# uno.net
KiCad netlist of a schematic drawn in EAGLE
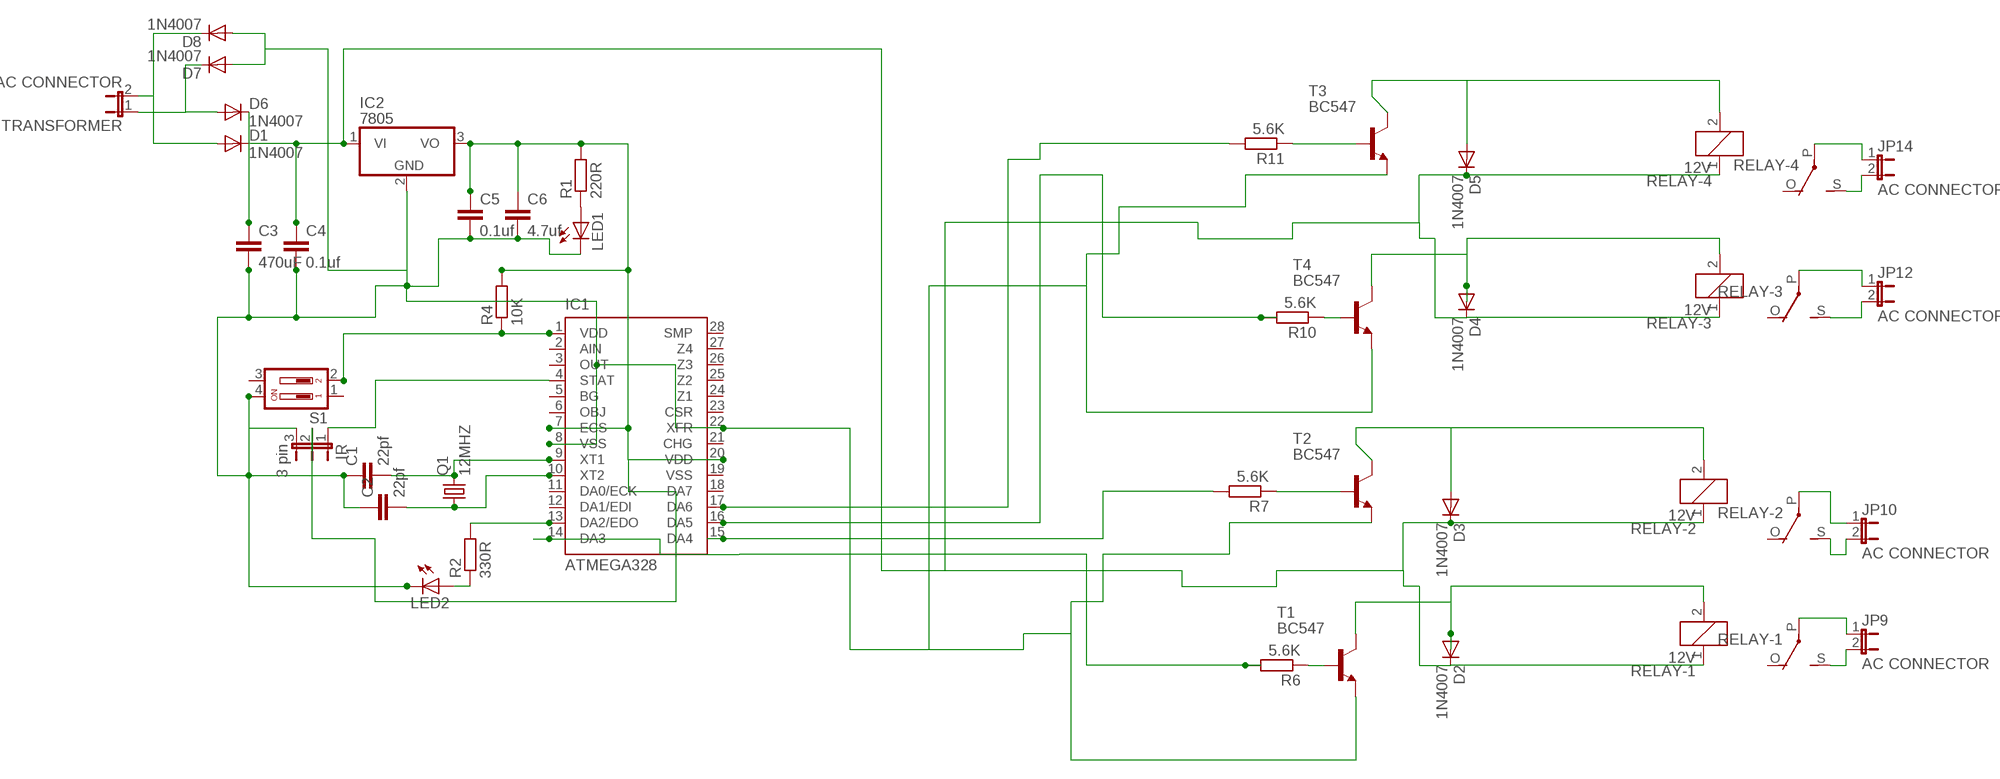
[diagram p0: schematic, sheet 1]

(export (version "E")
  (design (tool "Eeschema 10.0.6"))
  (components
    (comp (ref "C1")
      (value "22pf")
      (footprint "eagle-import:C2.5-2")
      (libsource (lib "eagle-import") (part "C2.5/2"))
    )
    (comp (ref "C2")
      (value "22pf")
      (footprint "eagle-import:C2.5-2")
      (libsource (lib "eagle-import") (part "C2.5/2"))
    )
    (comp (ref "C3")
      (value "470uF")
      (footprint "eagle-import:C2.5-2")
      (libsource (lib "eagle-import") (part "C2.5/2"))
    )
    (comp (ref "C4")
      (value "0.1uf")
      (footprint "eagle-import:C2.5-2")
      (libsource (lib "eagle-import") (part "C2.5/2"))
    )
    (comp (ref "C5")
      (value "0.1uf")
      (footprint "eagle-import:C2.5-2")
      (libsource (lib "eagle-import") (part "C2.5/2"))
    )
    (comp (ref "C6")
      (value "4.7uf")
      (footprint "eagle-import:C2.5-2")
      (libsource (lib "eagle-import") (part "C2.5/2"))
    )
    (comp (ref "D1")
      (value "1N4007")
      (footprint "eagle-import:DO41-10")
      (libsource (lib "eagle-import") (part "1N4004"))
    )
    (comp (ref "D2")
      (value "1N4007")
      (footprint "eagle-import:DO41-10")
      (libsource (lib "eagle-import") (part "1N4004"))
    )
    (comp (ref "D3")
      (value "1N4007")
      (footprint "eagle-import:DO41-10")
      (libsource (lib "eagle-import") (part "1N4004"))
    )
    (comp (ref "D4")
      (value "1N4007")
      (footprint "eagle-import:DO41-10")
      (libsource (lib "eagle-import") (part "1N4004"))
    )
    (comp (ref "D5")
      (value "1N4007")
      (footprint "eagle-import:DO41-10")
      (libsource (lib "eagle-import") (part "1N4004"))
    )
    (comp (ref "D6")
      (value "1N4007")
      (footprint "eagle-import:DO41-10")
      (libsource (lib "eagle-import") (part "1N4004"))
    )
    (comp (ref "D7")
      (value "1N4007")
      (footprint "eagle-import:DO41-10")
      (libsource (lib "eagle-import") (part "1N4004"))
    )
    (comp (ref "D8")
      (value "1N4007")
      (footprint "eagle-import:DO41-10")
      (libsource (lib "eagle-import") (part "1N4004"))
    )
    (comp (ref "IC1")
      (value "ATMEGA328")
      (footprint "eagle-import:DIL28-3")
      (libsource (lib "eagle-import") (part "QT9701BD"))
    )
    (comp (ref "IC2")
      (value "7805")
      (footprint "eagle-import:TO220V")
      (libsource (lib "eagle-import") (part "78TV6"))
    )
    (comp (ref "IR")
      (value "3 pin")
      (footprint "eagle-import:JP2")
      (libsource (lib "eagle-import") (part "JP2E"))
    )
    (comp (ref "JP9")
      (value "AC CONNECTOR")
      (footprint "eagle-import:JP1")
      (libsource (lib "eagle-import") (part "JP1E"))
    )
    (comp (ref "JP10")
      (value "AC CONNECTOR")
      (footprint "eagle-import:JP1")
      (libsource (lib "eagle-import") (part "JP1E"))
    )
    (comp (ref "JP12")
      (value "AC CONNECTOR")
      (footprint "eagle-import:JP1")
      (libsource (lib "eagle-import") (part "JP1E"))
    )
    (comp (ref "JP14")
      (value "AC CONNECTOR")
      (footprint "eagle-import:JP1")
      (libsource (lib "eagle-import") (part "JP1E"))
    )
    (comp (ref "LED1")
      (value "LED3MM")
      (footprint "eagle-import:LED3MM")
      (libsource (lib "eagle-import") (part "LED3MM"))
    )
    (comp (ref "LED2")
      (value "LED3MM")
      (footprint "eagle-import:LED3MM")
      (libsource (lib "eagle-import") (part "LED3MM"))
    )
    (comp (ref "Q1")
      (value "12MHZ")
      (footprint "eagle-import:HC49_S")
      (libsource (lib "eagle-import") (part "CRYSTALHC49S"))
    )
    (comp (ref "R1")
      (value "220R")
      (footprint "eagle-import:0207_10")
      (libsource (lib "eagle-import") (part "R-EU_0207/10"))
    )
    (comp (ref "R2")
      (value "330R")
      (footprint "eagle-import:0207_10")
      (libsource (lib "eagle-import") (part "R-EU_0207/10"))
    )
    (comp (ref "R4")
      (value "10K")
      (footprint "eagle-import:0207_10")
      (libsource (lib "eagle-import") (part "R-EU_0207/10"))
    )
    (comp (ref "R6")
      (value "5.6K")
      (footprint "eagle-import:0204_7")
      (libsource (lib "eagle-import") (part "R-EU_0204/7"))
    )
    (comp (ref "R7")
      (value "5.6K")
      (footprint "eagle-import:0204_7")
      (libsource (lib "eagle-import") (part "R-EU_0204/7"))
    )
    (comp (ref "R10")
      (value "5.6K")
      (footprint "eagle-import:0204_7")
      (libsource (lib "eagle-import") (part "R-EU_0204/7"))
    )
    (comp (ref "R11")
      (value "5.6K")
      (footprint "eagle-import:0204_7")
      (libsource (lib "eagle-import") (part "R-EU_0204/7"))
    )
    (comp (ref "RELAY-1")
      (value "12V")
      (footprint "eagle-import:G5LE")
      (libsource (lib "eagle-import") (part "G5L"))
    )
    (comp (ref "RELAY-2")
      (value "12V")
      (footprint "eagle-import:G5LE")
      (libsource (lib "eagle-import") (part "G5L"))
    )
    (comp (ref "RELAY-3")
      (value "12V")
      (footprint "eagle-import:G5LE")
      (libsource (lib "eagle-import") (part "G5L"))
    )
    (comp (ref "RELAY-4")
      (value "12V")
      (footprint "eagle-import:G5LE")
      (libsource (lib "eagle-import") (part "G5L"))
    )
    (comp (ref "S1")
      (value "DP02")
      (footprint "eagle-import:DP-02")
      (fields (field (name "MPN") "MCDP02"))
      (libsource (lib "eagle-import") (part "DP02"))
    )
    (comp (ref "T1")
      (value "BC547")
      (footprint "eagle-import:TO92")
      (libsource (lib "eagle-import") (part "BC547"))
    )
    (comp (ref "T2")
      (value "BC547")
      (footprint "eagle-import:TO92")
      (libsource (lib "eagle-import") (part "BC547"))
    )
    (comp (ref "T3")
      (value "BC547")
      (footprint "eagle-import:TO92")
      (libsource (lib "eagle-import") (part "BC547"))
    )
    (comp (ref "T4")
      (value "BC547")
      (footprint "eagle-import:TO92")
      (libsource (lib "eagle-import") (part "BC547"))
    )
    (comp (ref "TRANSFORMER")
      (value "AC CONNECTOR")
      (footprint "eagle-import:JP1")
      (libsource (lib "eagle-import") (part "JP1E"))
    )
  )
  (nets
    (net (code "1") (name "Net-(D1-PadA)") (class "Default")
      (node (ref "D1") (pin "A") (pinfunction "A_A") (pintype "passive"))
      (node (ref "D8") (pin "C") (pinfunction "C_C") (pintype "passive"))
      (node (ref "TRANSFORMER") (pin "2") (pinfunction "2_2") (pintype "passive"))
    )
    (net (code "2") (name "Net-(D6-PadA)") (class "Default")
      (node (ref "D6") (pin "A") (pinfunction "A_A") (pintype "passive"))
      (node (ref "D7") (pin "C") (pinfunction "C_C") (pintype "passive"))
      (node (ref "TRANSFORMER") (pin "1") (pinfunction "1_1") (pintype "passive"))
    )
    (net (code "3") (name "Net-(IC1-DA2{slash}EDO)") (class "Default")
      (node (ref "IC1") (pin "13") (pinfunction "DA2/EDO_13") (pintype "output"))
      (node (ref "R2") (pin "2") (pinfunction "2_2") (pintype "passive"))
    )
    (net (code "4") (name "Net-(IC1-DA3)") (class "Default")
      (node (ref "IC1") (pin "14") (pinfunction "DA3_14") (pintype "output"))
      (node (ref "R6") (pin "2") (pinfunction "2_2") (pintype "passive"))
    )
    (net (code "5") (name "Net-(IC1-DA4)") (class "Default")
      (node (ref "IC1") (pin "15") (pinfunction "DA4_15") (pintype "output"))
      (node (ref "R7") (pin "2") (pinfunction "2_2") (pintype "passive"))
    )
    (net (code "6") (name "Net-(IC1-DA5)") (class "Default")
      (node (ref "IC1") (pin "16") (pinfunction "DA5_16") (pintype "output"))
      (node (ref "R10") (pin "2") (pinfunction "2_2") (pintype "passive"))
    )
    (net (code "7") (name "Net-(IC1-DA6)") (class "Default")
      (node (ref "IC1") (pin "17") (pinfunction "DA6_17") (pintype "output"))
      (node (ref "R11") (pin "2") (pinfunction "2_2") (pintype "passive"))
    )
    (net (code "8") (name "Net-(IC1-ECS)") (class "Default")
      (node (ref "C5") (pin "1") (pinfunction "1_1") (pintype "passive"))
      (node (ref "C6") (pin "1") (pinfunction "1_1") (pintype "passive"))
      (node (ref "IC1") (pin "20") (pinfunction "VDD_20") (pintype "input"))
      (node (ref "IC1") (pin "7") (pinfunction "ECS_7") (pintype "output"))
      (node (ref "IC2") (pin "3") (pinfunction "VO_3") (pintype "passive"))
      (node (ref "IR") (pin "2") (pinfunction "2_2") (pintype "passive"))
      (node (ref "R1") (pin "2") (pinfunction "2_2") (pintype "passive"))
      (node (ref "R4") (pin "2") (pinfunction "2_2") (pintype "passive"))
    )
    (net (code "9") (name "Net-(IC1-STAT)") (class "Default")
      (node (ref "IC1") (pin "4") (pinfunction "STAT_4") (pintype "output"))
      (node (ref "IR") (pin "1") (pinfunction "1_1") (pintype "passive"))
    )
    (net (code "10") (name "Net-(IC1-VDD-Pad1)") (class "Default")
      (node (ref "IC1") (pin "1") (pinfunction "VDD_1") (pintype "input"))
      (node (ref "R4") (pin "1") (pinfunction "1_1") (pintype "passive"))
      (node (ref "S1") (pin "2") (pinfunction "2_2") (pintype "passive"))
    )
    (net (code "11") (name "Net-(IC1-XFR)") (class "Default")
      (node (ref "C1") (pin "1") (pinfunction "1_1") (pintype "passive"))
      (node (ref "C2") (pin "1") (pinfunction "1_1") (pintype "passive"))
      (node (ref "C3") (pin "2") (pinfunction "2_2") (pintype "passive"))
      (node (ref "C4") (pin "2") (pinfunction "2_2") (pintype "passive"))
      (node (ref "C5") (pin "2") (pinfunction "2_2") (pintype "passive"))
      (node (ref "C6") (pin "2") (pinfunction "2_2") (pintype "passive"))
      (node (ref "D7") (pin "A") (pinfunction "A_A") (pintype "passive"))
      (node (ref "D8") (pin "A") (pinfunction "A_A") (pintype "passive"))
      (node (ref "IC1") (pin "22") (pinfunction "XFR_22") (pintype "output"))
      (node (ref "IC1") (pin "8") (pinfunction "VSS_8") (pintype "input"))
      (node (ref "IC2") (pin "2") (pinfunction "GND_2") (pintype "passive"))
      (node (ref "IR") (pin "3") (pinfunction "3_3") (pintype "passive"))
      (node (ref "LED1") (pin "K") (pinfunction "C_K") (pintype "passive"))
      (node (ref "LED2") (pin "K") (pinfunction "C_K") (pintype "passive"))
      (node (ref "S1") (pin "4") (pinfunction "4_4") (pintype "passive"))
      (node (ref "T1") (pin "1") (pinfunction "E_1") (pintype "passive"))
      (node (ref "T2") (pin "1") (pinfunction "E_1") (pintype "passive"))
      (node (ref "T3") (pin "1") (pinfunction "E_1") (pintype "passive"))
      (node (ref "T4") (pin "1") (pinfunction "E_1") (pintype "passive"))
    )
    (net (code "12") (name "Net-(IC1-XT1)") (class "Default")
      (node (ref "C1") (pin "2") (pinfunction "2_2") (pintype "passive"))
      (node (ref "IC1") (pin "9") (pinfunction "XT1_9") (pintype "input"))
      (node (ref "Q1") (pin "2") (pinfunction "2_2") (pintype "passive"))
    )
    (net (code "13") (name "Net-(IC1-XT2)") (class "Default")
      (node (ref "C2") (pin "2") (pinfunction "2_2") (pintype "passive"))
      (node (ref "IC1") (pin "10") (pinfunction "XT2_10") (pintype "output"))
      (node (ref "Q1") (pin "1") (pinfunction "1_1") (pintype "passive"))
    )
    (net (code "14") (name "Net-(IC2-VI)") (class "Default")
      (node (ref "C3") (pin "1") (pinfunction "1_1") (pintype "passive"))
      (node (ref "C4") (pin "1") (pinfunction "1_1") (pintype "passive"))
      (node (ref "D1") (pin "C") (pinfunction "C_C") (pintype "passive"))
      (node (ref "D2") (pin "C") (pinfunction "C_C") (pintype "passive"))
      (node (ref "D3") (pin "C") (pinfunction "C_C") (pintype "passive"))
      (node (ref "D4") (pin "C") (pinfunction "C_C") (pintype "passive"))
      (node (ref "D5") (pin "C") (pinfunction "C_C") (pintype "passive"))
      (node (ref "D6") (pin "C") (pinfunction "C_C") (pintype "passive"))
      (node (ref "IC2") (pin "1") (pinfunction "VI_1") (pintype "input"))
      (node (ref "RELAY-1") (pin "1") (pinfunction "1_1") (pintype "passive"))
      (node (ref "RELAY-2") (pin "1") (pinfunction "1_1") (pintype "passive"))
      (node (ref "RELAY-3") (pin "1") (pinfunction "1_1") (pintype "passive"))
      (node (ref "RELAY-4") (pin "1") (pinfunction "1_1") (pintype "passive"))
    )
    (net (code "15") (name "Net-(JP9-Pad1)") (class "Default")
      (node (ref "JP9") (pin "1") (pinfunction "1_1") (pintype "passive"))
      (node (ref "RELAY-1") (pin "P") (pinfunction "P_P") (pintype "passive"))
    )
    (net (code "16") (name "Net-(JP9-Pad2)") (class "Default")
      (node (ref "JP9") (pin "2") (pinfunction "2_2") (pintype "passive"))
      (node (ref "RELAY-1") (pin "S") (pinfunction "S_S") (pintype "passive"))
    )
    (net (code "17") (name "Net-(JP10-Pad1)") (class "Default")
      (node (ref "JP10") (pin "1") (pinfunction "1_1") (pintype "passive"))
      (node (ref "RELAY-2") (pin "P") (pinfunction "P_P") (pintype "passive"))
    )
    (net (code "18") (name "Net-(JP10-Pad2)") (class "Default")
      (node (ref "JP10") (pin "2") (pinfunction "2_2") (pintype "passive"))
      (node (ref "RELAY-2") (pin "S") (pinfunction "S_S") (pintype "passive"))
    )
    (net (code "19") (name "Net-(JP12-Pad1)") (class "Default")
      (node (ref "JP12") (pin "1") (pinfunction "1_1") (pintype "passive"))
      (node (ref "RELAY-3") (pin "P") (pinfunction "P_P") (pintype "passive"))
    )
    (net (code "20") (name "Net-(JP12-Pad2)") (class "Default")
      (node (ref "JP12") (pin "2") (pinfunction "2_2") (pintype "passive"))
      (node (ref "RELAY-3") (pin "S") (pinfunction "S_S") (pintype "passive"))
    )
    (net (code "21") (name "Net-(JP14-Pad1)") (class "Default")
      (node (ref "JP14") (pin "1") (pinfunction "1_1") (pintype "passive"))
      (node (ref "RELAY-4") (pin "P") (pinfunction "P_P") (pintype "passive"))
    )
    (net (code "22") (name "Net-(JP14-Pad2)") (class "Default")
      (node (ref "JP14") (pin "2") (pinfunction "2_2") (pintype "passive"))
      (node (ref "RELAY-4") (pin "S") (pinfunction "S_S") (pintype "passive"))
    )
    (net (code "23") (name "Net-(LED1-PadA)") (class "Default")
      (node (ref "LED1") (pin "A") (pinfunction "A_A") (pintype "passive"))
      (node (ref "R1") (pin "1") (pinfunction "1_1") (pintype "passive"))
    )
    (net (code "24") (name "Net-(LED2-PadA)") (class "Default")
      (node (ref "LED2") (pin "A") (pinfunction "A_A") (pintype "passive"))
      (node (ref "R2") (pin "1") (pinfunction "1_1") (pintype "passive"))
    )
    (net (code "25") (name "Net-(T1-B)") (class "Default")
      (node (ref "R6") (pin "1") (pinfunction "1_1") (pintype "passive"))
      (node (ref "T1") (pin "2") (pinfunction "B_2") (pintype "passive"))
    )
    (net (code "26") (name "Net-(T1-C)") (class "Default")
      (node (ref "D2") (pin "A") (pinfunction "A_A") (pintype "passive"))
      (node (ref "RELAY-1") (pin "2") (pinfunction "2_2") (pintype "passive"))
      (node (ref "T1") (pin "3") (pinfunction "C_3") (pintype "passive"))
    )
    (net (code "27") (name "Net-(T2-B)") (class "Default")
      (node (ref "R7") (pin "1") (pinfunction "1_1") (pintype "passive"))
      (node (ref "T2") (pin "2") (pinfunction "B_2") (pintype "passive"))
    )
    (net (code "28") (name "Net-(T2-C)") (class "Default")
      (node (ref "D3") (pin "A") (pinfunction "A_A") (pintype "passive"))
      (node (ref "RELAY-2") (pin "2") (pinfunction "2_2") (pintype "passive"))
      (node (ref "T2") (pin "3") (pinfunction "C_3") (pintype "passive"))
    )
    (net (code "29") (name "Net-(T3-B)") (class "Default")
      (node (ref "R11") (pin "1") (pinfunction "1_1") (pintype "passive"))
      (node (ref "T3") (pin "2") (pinfunction "B_2") (pintype "passive"))
    )
    (net (code "30") (name "Net-(T3-C)") (class "Default")
      (node (ref "D5") (pin "A") (pinfunction "A_A") (pintype "passive"))
      (node (ref "RELAY-4") (pin "2") (pinfunction "2_2") (pintype "passive"))
      (node (ref "T3") (pin "3") (pinfunction "C_3") (pintype "passive"))
    )
    (net (code "31") (name "Net-(T4-B)") (class "Default")
      (node (ref "R10") (pin "1") (pinfunction "1_1") (pintype "passive"))
      (node (ref "T4") (pin "2") (pinfunction "B_2") (pintype "passive"))
    )
    (net (code "32") (name "Net-(T4-C)") (class "Default")
      (node (ref "D4") (pin "A") (pinfunction "A_A") (pintype "passive"))
      (node (ref "RELAY-3") (pin "2") (pinfunction "2_2") (pintype "passive"))
      (node (ref "T4") (pin "3") (pinfunction "C_3") (pintype "passive"))
    )
    (net (code "33") (name "unconnected-(IC1-AIN-Pad2)") (class "Default")
      (node (ref "IC1") (pin "2") (pinfunction "AIN_2") (pintype "input"))
    )
    (net (code "34") (name "unconnected-(IC1-BG-Pad5)") (class "Default")
      (node (ref "IC1") (pin "5") (pinfunction "BG_5") (pintype "input"))
    )
    (net (code "35") (name "unconnected-(IC1-CHG-Pad21)") (class "Default")
      (node (ref "IC1") (pin "21") (pinfunction "CHG_21") (pintype "output"))
    )
    (net (code "36") (name "unconnected-(IC1-CSR-Pad23)") (class "Default")
      (node (ref "IC1") (pin "23") (pinfunction "CSR_23") (pintype "output"))
    )
    (net (code "37") (name "unconnected-(IC1-DA0{slash}ECK-Pad11)") (class "Default")
      (node (ref "IC1") (pin "11") (pinfunction "DA0/ECK_11") (pintype "output"))
    )
    (net (code "38") (name "unconnected-(IC1-DA1{slash}EDI-Pad12)") (class "Default")
      (node (ref "IC1") (pin "12") (pinfunction "DA1/EDI_12") (pintype "output"))
    )
    (net (code "39") (name "unconnected-(IC1-DA7-Pad18)") (class "Default")
      (node (ref "IC1") (pin "18") (pinfunction "DA7_18") (pintype "output"))
    )
    (net (code "40") (name "unconnected-(IC1-OBJ-Pad6)") (class "Default")
      (node (ref "IC1") (pin "6") (pinfunction "OBJ_6") (pintype "input"))
    )
    (net (code "41") (name "unconnected-(IC1-OUT-Pad3)") (class "Default")
      (node (ref "IC1") (pin "3") (pinfunction "OUT_3") (pintype "output"))
    )
    (net (code "42") (name "unconnected-(IC1-SMP-Pad28)") (class "Default")
      (node (ref "IC1") (pin "28") (pinfunction "SMP_28") (pintype "output"))
    )
    (net (code "43") (name "unconnected-(IC1-VSS-Pad19)") (class "Default")
      (node (ref "IC1") (pin "19") (pinfunction "VSS_19") (pintype "input"))
    )
    (net (code "44") (name "unconnected-(IC1-Z1-Pad24)") (class "Default")
      (node (ref "IC1") (pin "24") (pinfunction "Z1_24") (pintype "output"))
    )
    (net (code "45") (name "unconnected-(IC1-Z2-Pad25)") (class "Default")
      (node (ref "IC1") (pin "25") (pinfunction "Z2_25") (pintype "output"))
    )
    (net (code "46") (name "unconnected-(IC1-Z3-Pad26)") (class "Default")
      (node (ref "IC1") (pin "26") (pinfunction "Z3_26") (pintype "output"))
    )
    (net (code "47") (name "unconnected-(IC1-Z4-Pad27)") (class "Default")
      (node (ref "IC1") (pin "27") (pinfunction "Z4_27") (pintype "output"))
    )
    (net (code "48") (name "unconnected-(RELAY-1-PadO)") (class "Default")
      (node (ref "RELAY-1") (pin "O") (pinfunction "O_O") (pintype "passive"))
    )
    (net (code "49") (name "unconnected-(RELAY-2-PadO)") (class "Default")
      (node (ref "RELAY-2") (pin "O") (pinfunction "O_O") (pintype "passive"))
    )
    (net (code "50") (name "unconnected-(RELAY-3-PadO)") (class "Default")
      (node (ref "RELAY-3") (pin "O") (pinfunction "O_O") (pintype "passive"))
    )
    (net (code "51") (name "unconnected-(RELAY-4-PadO)") (class "Default")
      (node (ref "RELAY-4") (pin "O") (pinfunction "O_O") (pintype "passive"))
    )
    (net (code "52") (name "unconnected-(S1-Pad1)") (class "Default")
      (node (ref "S1") (pin "1") (pinfunction "1_1") (pintype "passive"))
    )
    (net (code "53") (name "unconnected-(S1-Pad3)") (class "Default")
      (node (ref "S1") (pin "3") (pinfunction "3_3") (pintype "passive"))
    )
  )
)
